# 2019_PROPEEPROM.net
KiCad netlist of a schematic drawn in Altium Designer
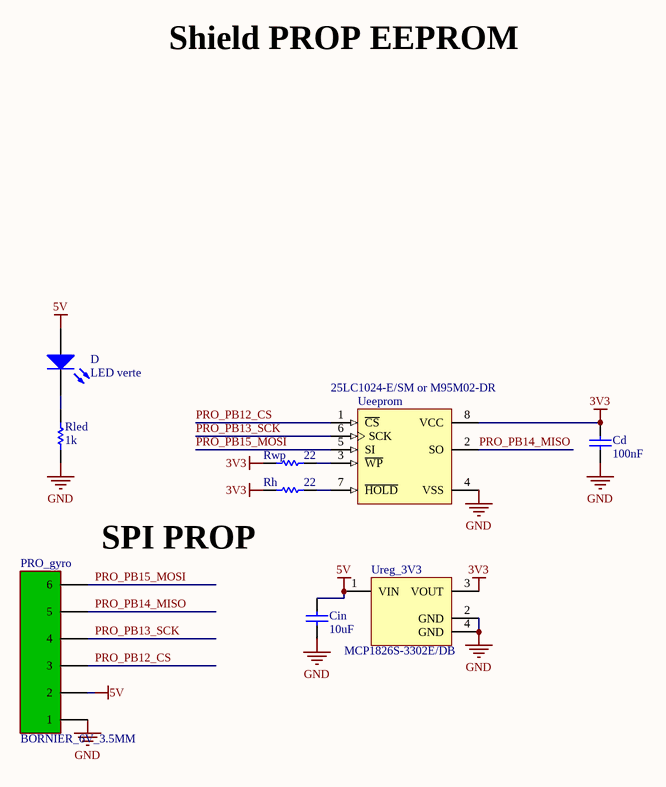
[diagram p0: 2019_PROPEEPROM.SchDoc]

(export (version "E")
  (design (tool "Eeschema 10.0.6"))
  (components
    (comp (ref "Cd")
      (value "100nF")
      (footprint "C0805_N")
      (description "Capacitor")
      (fields (field (name "PUBLISHER") "Altium Limited"))
      (libsource (lib "_ROBOT") (part "Condensateur"))
    )
    (comp (ref "Cin")
      (value "10uF")
      (footprint "C1206_N")
      (description "Capacitor")
      (fields (field (name "PUBLISHER") "Altium Limited"))
      (libsource (lib "DG_Condensateur") (part "Capacitor"))
    )
    (comp (ref "D")
      (value "LED verte")
      (footprint "LED_0805")
      (description "Typical LED")
      (fields (field (name "PUBLISHER") "Altium Limited"))
      (libsource (lib "_ROBOT") (part "LED"))
    )
    (comp (ref "PRO_gyro")
      (value "BORNIER_6V_3.5MM")
      (footprint "BORNIER_6V_3.5MM")
      (libsource (lib "Connecteur") (part "BORNIER_6V_3.5MM"))
    )
    (comp (ref "Rh")
      (value "22")
      (footprint "R1206_N")
      (description "Resistor")
      (fields (field (name "PUBLISHER") "Altium Limited"))
      (libsource (lib "_ROBOT") (part "Resistor"))
    )
    (comp (ref "Rled")
      (value "1k")
      (footprint "R1206_N")
      (description "Resistor")
      (fields (field (name "PUBLISHER") "Altium Limited"))
      (libsource (lib "_ROBOT") (part "Resistor"))
    )
    (comp (ref "Rwp")
      (value "22")
      (footprint "R1206_N")
      (description "Resistor")
      (fields (field (name "PUBLISHER") "Altium Limited"))
      (libsource (lib "_ROBOT") (part "Resistor"))
    )
    (comp (ref "Ueeprom")
      (value "25LC1024-E/SM or M95M02-DR")
      (footprint "SOIJ-SM8_N")
      (description "1 Mbit SPI Bus Serial EEPROM, 8-Pin SOIC, Extended Temperature")
      (fields (field (name "MANUFACTURER") "Microchip") (field (name "PARTNUMBER") "25LC1024-E/SM"))
      (libsource (lib "Microchip SPI Serial EEPROM") (part "25LC1024-E/SM"))
    )
    (comp (ref "Ureg_3V3")
      (value "MCP1826S-3302E/DB")
      (footprint "SOT223-4N")
      (description "1000 mA, Low Voltage, Low Quiescent Current LDO Regulator, 3-Pin SOT-223, Extended Temperature")
      (fields (field (name "PUBLISHER") "Altium Limited"))
      (libsource (lib "Microchip Power Mgt Line Regulator") (part "MCP1826S-3302E/DB"))
    )
  )
  (nets
    (net (code "1") (name "/PRO_PB12_CS") (class "Default")
      (node (ref "PRO_gyro") (pin "3") (pinfunction "3_3") (pintype "passive"))
      (node (ref "Ueeprom") (pin "1") (pinfunction "~{CS}_1") (pintype "input"))
    )
    (net (code "2") (name "/PRO_PB13_SCK") (class "Default")
      (node (ref "PRO_gyro") (pin "4") (pinfunction "4_4") (pintype "passive"))
      (node (ref "Ueeprom") (pin "6") (pinfunction "SCK_6") (pintype "input"))
    )
    (net (code "3") (name "/PRO_PB14_MISO") (class "Default")
      (node (ref "PRO_gyro") (pin "5") (pinfunction "5_5") (pintype "passive"))
      (node (ref "Ueeprom") (pin "2") (pinfunction "SO_2") (pintype "tri_state"))
    )
    (net (code "4") (name "/PRO_PB15_MOSI") (class "Default")
      (node (ref "PRO_gyro") (pin "6") (pinfunction "6_6") (pintype "passive"))
      (node (ref "Ueeprom") (pin "5") (pinfunction "SI_5") (pintype "input"))
    )
    (net (code "5") (name "3V3") (class "Default")
      (node (ref "Cd") (pin "2") (pinfunction "2_2") (pintype "passive"))
      (node (ref "Rh") (pin "2") (pinfunction "2_2") (pintype "passive"))
      (node (ref "Rwp") (pin "2") (pinfunction "2_2") (pintype "passive"))
      (node (ref "Ueeprom") (pin "8") (pinfunction "VCC_8") (pintype "power_in"))
      (node (ref "Ureg_3V3") (pin "3") (pinfunction "VOUT_3") (pintype "power_in"))
    )
    (net (code "6") (name "5V") (class "Default")
      (node (ref "Cin") (pin "2") (pinfunction "2_2") (pintype "passive"))
      (node (ref "D") (pin "1") (pinfunction "A_1") (pintype "passive"))
      (node (ref "PRO_gyro") (pin "2") (pinfunction "2_2") (pintype "passive"))
      (node (ref "Ureg_3V3") (pin "1") (pinfunction "VIN_1") (pintype "power_in"))
    )
    (net (code "7") (name "GND") (class "Default")
      (node (ref "Cd") (pin "1") (pinfunction "1_1") (pintype "passive"))
      (node (ref "Cin") (pin "1") (pinfunction "1_1") (pintype "passive"))
      (node (ref "PRO_gyro") (pin "1") (pinfunction "1_1") (pintype "passive"))
      (node (ref "Rled") (pin "1") (pinfunction "1_1") (pintype "passive"))
      (node (ref "Ueeprom") (pin "4") (pinfunction "VSS_4") (pintype "power_in"))
      (node (ref "Ureg_3V3") (pin "2") (pinfunction "GND_2") (pintype "power_in"))
      (node (ref "Ureg_3V3") (pin "4") (pinfunction "GND_4") (pintype "power_in"))
    )
    (net (code "8") (name "Net-(D-K)") (class "Default")
      (node (ref "D") (pin "2") (pinfunction "K_2") (pintype "passive"))
      (node (ref "Rled") (pin "2") (pinfunction "2_2") (pintype "passive"))
    )
    (net (code "9") (name "Net-(Ueeprom-~{HOLD})") (class "Default")
      (node (ref "Rh") (pin "1") (pinfunction "1_1") (pintype "passive"))
      (node (ref "Ueeprom") (pin "7") (pinfunction "~{HOLD}_7") (pintype "input"))
    )
    (net (code "10") (name "Net-(Ueeprom-~{WP})") (class "Default")
      (node (ref "Rwp") (pin "1") (pinfunction "1_1") (pintype "passive"))
      (node (ref "Ueeprom") (pin "3") (pinfunction "~{WP}_3") (pintype "input"))
    )
  )
)
